# RedBoard_Turbo.net
KiCad netlist of a schematic drawn in EAGLE
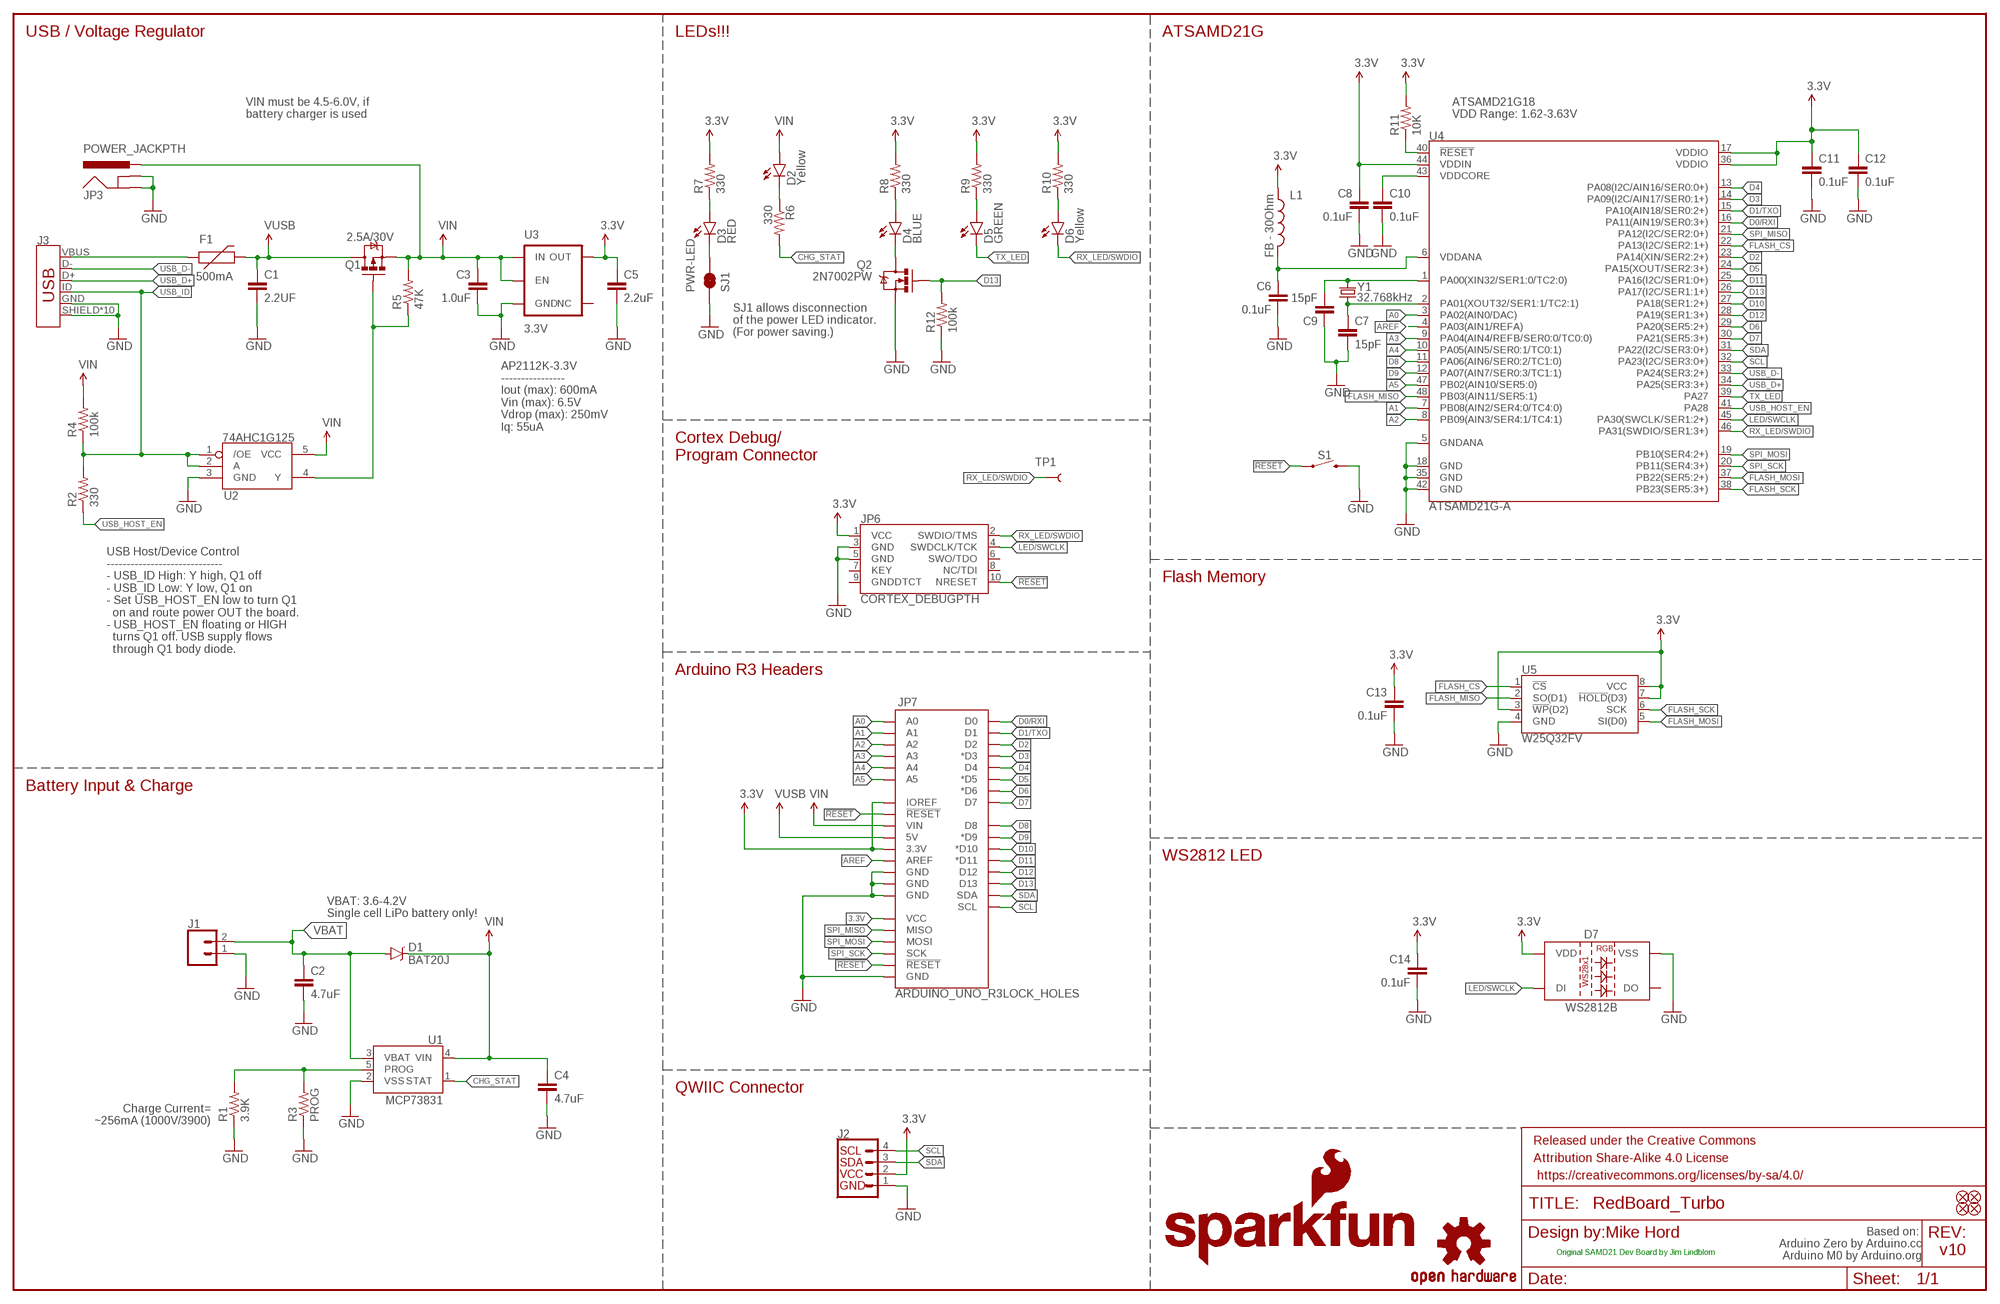
[diagram p0: schematic, sheet 1]

(export (version "E")
  (design (tool "Eeschema 10.0.6"))
  (components
    (comp (ref "C1")
      (value "2.2UF")
      (footprint "eagle-import:1206@1")
      (libsource (lib "eagle-import") (part "2.2UF50V10%(1206)"))
    )
    (comp (ref "C2")
      (value "4.7uF")
      (footprint "eagle-import:0603-CAP")
      (libsource (lib "eagle-import") (part "4.7UF-6.3V-10%(0603)0603"))
    )
    (comp (ref "C3")
      (value "1.0uF")
      (footprint "eagle-import:0805")
      (libsource (lib "eagle-import") (part "1.0UF-0805-25V-10%"))
    )
    (comp (ref "C4")
      (value "4.7uF")
      (footprint "eagle-import:0603-CAP")
      (libsource (lib "eagle-import") (part "4.7UF-6.3V-10%(0603)0603"))
    )
    (comp (ref "C5")
      (value "2.2uF")
      (footprint "eagle-import:0603-CAP")
      (libsource (lib "eagle-import") (part "2.2UF-10V-20%(0603)"))
    )
    (comp (ref "C6")
      (value "0.1uF")
      (footprint "eagle-import:0603-CAP")
      (libsource (lib "eagle-import") (part "0.1UF-25V(+80/-20%)(0603)"))
    )
    (comp (ref "C7")
      (value "15pF")
      (footprint "eagle-import:0603-CAP")
      (libsource (lib "eagle-import") (part "15PF-50V-5%(0603)"))
    )
    (comp (ref "C8")
      (value "0.1uF")
      (footprint "eagle-import:0603-CAP")
      (libsource (lib "eagle-import") (part "0.1UF-25V(+80/-20%)(0603)"))
    )
    (comp (ref "C9")
      (value "15pF")
      (footprint "eagle-import:0603-CAP")
      (libsource (lib "eagle-import") (part "15PF-50V-5%(0603)"))
    )
    (comp (ref "C10")
      (value "0.1uF")
      (footprint "eagle-import:0603-CAP")
      (libsource (lib "eagle-import") (part "0.1UF-25V(+80/-20%)(0603)"))
    )
    (comp (ref "C11")
      (value "0.1uF")
      (footprint "eagle-import:0603-CAP")
      (libsource (lib "eagle-import") (part "0.1UF-25V(+80/-20%)(0603)"))
    )
    (comp (ref "C12")
      (value "0.1uF")
      (footprint "eagle-import:0603-CAP")
      (libsource (lib "eagle-import") (part "0.1UF-25V(+80/-20%)(0603)"))
    )
    (comp (ref "C13")
      (value "0.1uF")
      (footprint "eagle-import:0603-CAP")
      (libsource (lib "eagle-import") (part "0.1UF-25V(+80/-20%)(0603)"))
    )
    (comp (ref "C14")
      (value "0.1uF")
      (footprint "eagle-import:0603-CAP")
      (libsource (lib "eagle-import") (part "0.1UF-25V(+80/-20%)(0603)"))
    )
    (comp (ref "D1")
      (value "BAT20J")
      (footprint "eagle-import:SOD-323")
      (libsource (lib "eagle-import") (part "DIODE-SCHOTTKY-BAT20J"))
    )
    (comp (ref "D2")
      (value "Yellow")
      (footprint "eagle-import:LED-0603")
      (libsource (lib "eagle-import") (part "LED-YELLOW0603"))
    )
    (comp (ref "D3")
      (value "RED")
      (footprint "eagle-import:LED-0603")
      (libsource (lib "eagle-import") (part "LED-RED0603"))
    )
    (comp (ref "D4")
      (value "BLUE")
      (footprint "eagle-import:LED-0603")
      (libsource (lib "eagle-import") (part "LED-BLUE0603"))
    )
    (comp (ref "D5")
      (value "GREEN")
      (footprint "eagle-import:LED-0603")
      (libsource (lib "eagle-import") (part "LED-GREEN0603"))
    )
    (comp (ref "D6")
      (value "Yellow")
      (footprint "eagle-import:LED-0603")
      (libsource (lib "eagle-import") (part "LED-YELLOW0603"))
    )
    (comp (ref "D7")
      (value "WS2812B")
      (footprint "eagle-import:WS2812B")
      (libsource (lib "eagle-import") (part "WS2812B"))
    )
    (comp (ref "F1")
      (value "500mA")
      (footprint "eagle-import:PTC-1206")
      (libsource (lib "eagle-import") (part "PTCSMD"))
    )
    (comp (ref "FID1")
      (value "FIDUCIAL1X2")
      (footprint "eagle-import:FIDUCIAL-1X2")
      (libsource (lib "eagle-import") (part "FIDUCIAL1X2"))
    )
    (comp (ref "FID2")
      (value "FIDUCIAL1X2")
      (footprint "eagle-import:FIDUCIAL-1X2")
      (libsource (lib "eagle-import") (part "FIDUCIAL1X2"))
    )
    (comp (ref "FID3")
      (value "FIDUCIAL1X2")
      (footprint "eagle-import:FIDUCIAL-1X2")
      (libsource (lib "eagle-import") (part "FIDUCIAL1X2"))
    )
    (comp (ref "FID4")
      (value "FIDUCIAL1X2")
      (footprint "eagle-import:FIDUCIAL-1X2")
      (libsource (lib "eagle-import") (part "FIDUCIAL1X2"))
    )
    (comp (ref "FRAME1")
      (value "FRAME-LEDGER")
      (footprint "eagle-import:CREATIVE_COMMONS")
      (libsource (lib "eagle-import") (part "FRAME-LEDGER"))
    )
    (comp (ref "J1")
      (value "CONN_02JST-PTH-2")
      (footprint "eagle-import:JST-2-PTH")
      (libsource (lib "eagle-import") (part "CONN_02JST-PTH-2"))
    )
    (comp (ref "J2")
      (value "QWIIC_CONNECTORJS-1MM")
      (footprint "eagle-import:1X04_1MM_RA")
      (libsource (lib "eagle-import") (part "QWIIC_CONNECTORJS-1MM"))
    )
    (comp (ref "J3")
      (value "USB_MICRO-B_HALF_PTH_MILL")
      (footprint "eagle-import:USB-MICROB-PTH-MILL")
      (libsource (lib "eagle-import") (part "USB_MICRO-B_HALF_PTH_MILL"))
    )
    (comp (ref "JP3")
      (value "POWER_JACKPTH")
      (footprint "eagle-import:POWER_JACK_PTH")
      (libsource (lib "eagle-import") (part "POWER_JACKPTH"))
    )
    (comp (ref "JP6")
      (value "CORTEX_DEBUGPTH")
      (footprint "eagle-import:2X5-PTH-1.27MM")
      (libsource (lib "eagle-import") (part "CORTEX_DEBUGPTH"))
    )
    (comp (ref "JP7")
      (value "ARDUINO_UNO_R3LOCK_HOLES")
      (footprint "eagle-import:ARDUINO_R3_LOCK_HOLES")
      (libsource (lib "eagle-import") (part "ARDUINO_UNO_R3LOCK_HOLES"))
    )
    (comp (ref "L1")
      (value "FB - 30Ohm")
      (footprint "eagle-import:0603")
      (libsource (lib "eagle-import") (part "INDUCTOR0603"))
    )
    (comp (ref "LOGO1")
      (value "SFE_LOGO_NAME_FLAME.2_INCH")
      (footprint "eagle-import:SFE_LOGO_NAME_FLAME_.2")
      (libsource (lib "eagle-import") (part "SFE_LOGO_NAME_FLAME.2_INCH"))
    )
    (comp (ref "LOGO2")
      (value "SFE_LOGO_NAME_FLAME.3_INCH")
      (footprint "eagle-import:SFE_LOGO_NAME_FLAME_.3")
      (libsource (lib "eagle-import") (part "SFE_LOGO_NAME_FLAME.3_INCH"))
    )
    (comp (ref "LOGO3")
      (value "OSHW-LOGOS")
      (footprint "eagle-import:OSHW-LOGO-S")
      (libsource (lib "eagle-import") (part "OSHW-LOGOS"))
    )
    (comp (ref "LOGO4")
      (value "OSHW-LOGOL")
      (footprint "eagle-import:OSHW-LOGO-L")
      (libsource (lib "eagle-import") (part "OSHW-LOGOL"))
    )
    (comp (ref "Q1")
      (value "2.5A/30V")
      (footprint "eagle-import:SOT23-3")
      (libsource (lib "eagle-import") (part "MOSFET-PCHANNELDMG2307L"))
    )
    (comp (ref "Q2")
      (value "2N7002PW")
      (footprint "eagle-import:SOT323")
      (libsource (lib "eagle-import") (part "MOSFET-NCHANNEL2N7002PW"))
    )
    (comp (ref "R1")
      (value "3.9K")
      (footprint "eagle-import:0603")
      (libsource (lib "eagle-import") (part "3.9KOHM1/10W1%(0603)"))
    )
    (comp (ref "R2")
      (value "330")
      (footprint "eagle-import:0603-RES")
      (libsource (lib "eagle-import") (part "330OHM1/10W1%(0603)"))
    )
    (comp (ref "R3")
      (value "PROG")
      (footprint "eagle-import:1_6W-RES")
      (libsource (lib "eagle-import") (part "RESISTORPTH-1/6W"))
    )
    (comp (ref "R4")
      (value "100k")
      (footprint "eagle-import:0603-RES")
      (libsource (lib "eagle-import") (part "100KOHM-1/10W-1%(0603)"))
    )
    (comp (ref "R5")
      (value "47K")
      (footprint "eagle-import:0603-RES")
      (libsource (lib "eagle-import") (part "47KOHM1/10W1%(0603)"))
    )
    (comp (ref "R6")
      (value "330")
      (footprint "eagle-import:0603-RES")
      (libsource (lib "eagle-import") (part "330OHM1/10W1%(0603)"))
    )
    (comp (ref "R7")
      (value "330")
      (footprint "eagle-import:0603-RES")
      (libsource (lib "eagle-import") (part "330OHM1/10W1%(0603)"))
    )
    (comp (ref "R8")
      (value "330")
      (footprint "eagle-import:0603-RES")
      (libsource (lib "eagle-import") (part "330OHM1/10W1%(0603)"))
    )
    (comp (ref "R9")
      (value "330")
      (footprint "eagle-import:0603-RES")
      (libsource (lib "eagle-import") (part "330OHM1/10W1%(0603)"))
    )
    (comp (ref "R10")
      (value "330")
      (footprint "eagle-import:0603-RES")
      (libsource (lib "eagle-import") (part "330OHM1/10W1%(0603)"))
    )
    (comp (ref "R11")
      (value "10K")
      (footprint "eagle-import:0603-RES")
      (libsource (lib "eagle-import") (part "10KOHM-1/10W-1%(0603)0603"))
    )
    (comp (ref "R12")
      (value "100k")
      (footprint "eagle-import:0603-RES")
      (libsource (lib "eagle-import") (part "100KOHM-1/10W-1%(0603)"))
    )
    (comp (ref "S1")
      (value "MOMENTARY-SWITCH-SPST-SMD-5.2-TALL-REDUNDANT")
      (footprint "eagle-import:TACTILE_SWITCH_SMD_5.2MM")
      (libsource (lib "eagle-import") (part "MOMENTARY-SWITCH-SPST-SMD-5.2-TALL-REDUNDANT"))
    )
    (comp (ref "SJ1")
      (value "PWR-LED")
      (footprint "eagle-import:PAD-JUMPER-2-NC_BY_TRACE_NO_SILK")
      (libsource (lib "eagle-import") (part "JUMPER-PAD-2-NC_BY_TRACENO_SILK"))
    )
    (comp (ref "TP1")
      (value "TEST-POINTTP_15TH_THRU")
      (footprint "eagle-import:TP_15TH")
      (libsource (lib "eagle-import") (part "TEST-POINTTP_15TH_THRU"))
    )
    (comp (ref "U1")
      (value "MCP73831")
      (footprint "eagle-import:SOT23-5")
      (libsource (lib "eagle-import") (part "MCP73831"))
    )
    (comp (ref "U2")
      (value "74AHC1G125")
      (footprint "eagle-import:SOT23-5")
      (libsource (lib "eagle-import") (part "74AHC1G125"))
    )
    (comp (ref "U3")
      (value "3.3V")
      (footprint "eagle-import:SOT23-5")
      (libsource (lib "eagle-import") (part "V_REG_AP2112K-3.3V"))
    )
    (comp (ref "U4")
      (value "ATSAMD21G-A")
      (footprint "eagle-import:TQFP-48")
      (libsource (lib "eagle-import") (part "ATSAMD21G-A"))
    )
    (comp (ref "U5")
      (value "W25Q32FV")
      (footprint "eagle-import:SOIC-8")
      (libsource (lib "eagle-import") (part "W25Q32FVSS"))
    )
    (comp (ref "Y1")
      (value "32.768kHz")
      (footprint "eagle-import:CRYSTAL-SMD-3.2X1.5MM")
      (libsource (lib "eagle-import") (part "CRYSTAL3.2X1.5MM"))
    )
  )
  (nets
    (net (code "1") (name "/~{RESET}") (class "Default")
      (node (ref "JP6") (pin "10") (pinfunction "NRESET_10") (pintype "bidirectional"))
      (node (ref "JP7") (pin "RESET@1") (pinfunction "~{RESET}_RESET@1") (pintype "bidirectional"))
      (node (ref "JP7") (pin "RESET@2") (pinfunction "~{RESET}_RESET@2") (pintype "bidirectional"))
      (node (ref "R11") (pin "1") (pinfunction "1_1") (pintype "passive"))
      (node (ref "S1") (pin "1") (pinfunction "1_1") (pintype "passive"))
      (node (ref "S1") (pin "2") (pinfunction "1_2") (pintype "passive"))
      (node (ref "U4") (pin "40") (pinfunction "~{RESET}_40") (pintype "bidirectional"))
    )
    (net (code "2") (name "3.3V") (class "Default")
      (node (ref "C11") (pin "1") (pinfunction "1_1") (pintype "passive"))
      (node (ref "C12") (pin "1") (pinfunction "1_1") (pintype "passive"))
      (node (ref "C13") (pin "1") (pinfunction "1_1") (pintype "passive"))
      (node (ref "C14") (pin "1") (pinfunction "1_1") (pintype "passive"))
      (node (ref "C5") (pin "1") (pinfunction "1_1") (pintype "passive"))
      (node (ref "C8") (pin "1") (pinfunction "1_1") (pintype "passive"))
      (node (ref "D7") (pin "1") (pinfunction "VDD_1") (pintype "bidirectional"))
      (node (ref "J2") (pin "2") (pinfunction "2_2") (pintype "power_in"))
      (node (ref "JP6") (pin "1") (pinfunction "VCC_1") (pintype "bidirectional"))
      (node (ref "JP7") (pin "3.3V") (pinfunction "3.3V_3.3V") (pintype "bidirectional"))
      (node (ref "JP7") (pin "IOREF") (pinfunction "IOREF_IOREF") (pintype "bidirectional"))
      (node (ref "JP7") (pin "VCC") (pinfunction "VCC_VCC") (pintype "bidirectional"))
      (node (ref "L1") (pin "1") (pinfunction "1_1") (pintype "passive"))
      (node (ref "R10") (pin "2") (pinfunction "2_2") (pintype "passive"))
      (node (ref "R11") (pin "2") (pinfunction "2_2") (pintype "passive"))
      (node (ref "R7") (pin "2") (pinfunction "2_2") (pintype "passive"))
      (node (ref "R8") (pin "2") (pinfunction "2_2") (pintype "passive"))
      (node (ref "R9") (pin "2") (pinfunction "2_2") (pintype "passive"))
      (node (ref "U3") (pin "5") (pinfunction "OUT_5") (pintype "passive"))
      (node (ref "U4") (pin "17") (pinfunction "VDDIO_17") (pintype "bidirectional"))
      (node (ref "U4") (pin "36") (pinfunction "VDDIO_36") (pintype "bidirectional"))
      (node (ref "U4") (pin "44") (pinfunction "VDDIN_44") (pintype "bidirectional"))
      (node (ref "U5") (pin "3") (pinfunction "~{WP}(D2)_3") (pintype "bidirectional"))
      (node (ref "U5") (pin "7") (pinfunction "~{HOLD}(D3)_7") (pintype "bidirectional"))
      (node (ref "U5") (pin "8") (pinfunction "VCC_8") (pintype "bidirectional"))
    )
    (net (code "3") (name "A0") (class "Default")
      (node (ref "JP7") (pin "A0") (pinfunction "A0_A0") (pintype "bidirectional"))
      (node (ref "U4") (pin "3") (pinfunction "PA02(AIN0/DAC)_3") (pintype "bidirectional"))
    )
    (net (code "4") (name "A1") (class "Default")
      (node (ref "JP7") (pin "A1") (pinfunction "A1_A1") (pintype "bidirectional"))
      (node (ref "U4") (pin "7") (pinfunction "PB08(AIN2/SER4:0/TC4:0)_7") (pintype "bidirectional"))
    )
    (net (code "5") (name "A2") (class "Default")
      (node (ref "JP7") (pin "A2") (pinfunction "A2_A2") (pintype "bidirectional"))
      (node (ref "U4") (pin "8") (pinfunction "PB09(AIN3/SER4:1/TC4:1)_8") (pintype "bidirectional"))
    )
    (net (code "6") (name "A3") (class "Default")
      (node (ref "JP7") (pin "A3") (pinfunction "A3_A3") (pintype "bidirectional"))
      (node (ref "U4") (pin "9") (pinfunction "PA04(AIN4/REFB/SER0:0/TC0:0)_9") (pintype "bidirectional"))
    )
    (net (code "7") (name "A4") (class "Default")
      (node (ref "JP7") (pin "A4") (pinfunction "A4_A4") (pintype "bidirectional"))
      (node (ref "U4") (pin "10") (pinfunction "PA05(AIN5/SER0:1/TC0:1)_10") (pintype "bidirectional"))
    )
    (net (code "8") (name "A5") (class "Default")
      (node (ref "JP7") (pin "A5") (pinfunction "A5_A5") (pintype "bidirectional"))
      (node (ref "U4") (pin "47") (pinfunction "PB02(AIN10/SER5:0)_47") (pintype "bidirectional"))
    )
    (net (code "9") (name "AREF") (class "Default")
      (node (ref "JP7") (pin "AREF") (pinfunction "AREF_AREF") (pintype "bidirectional"))
      (node (ref "U4") (pin "4") (pinfunction "PA03(AIN1/REFA)_4") (pintype "bidirectional"))
    )
    (net (code "10") (name "CHG_STAT") (class "Default")
      (node (ref "R6") (pin "2") (pinfunction "2_2") (pintype "passive"))
      (node (ref "U1") (pin "1") (pinfunction "STAT_1") (pintype "output"))
    )
    (net (code "11") (name "D0{slash}RXI") (class "Default")
      (node (ref "JP7") (pin "D0") (pinfunction "D0_D0") (pintype "bidirectional"))
      (node (ref "U4") (pin "16") (pinfunction "PA11(AIN19/SER0:3+)_16") (pintype "bidirectional"))
    )
    (net (code "12") (name "D1{slash}TXO") (class "Default")
      (node (ref "JP7") (pin "D1") (pinfunction "D1_D1") (pintype "bidirectional"))
      (node (ref "U4") (pin "15") (pinfunction "PA10(AIN18/SER0:2+)_15") (pintype "bidirectional"))
    )
    (net (code "13") (name "D2") (class "Default")
      (node (ref "JP7") (pin "D2") (pinfunction "D2_D2") (pintype "bidirectional"))
      (node (ref "U4") (pin "23") (pinfunction "PA14(XIN/SER2:2+)_23") (pintype "bidirectional"))
    )
    (net (code "14") (name "D3") (class "Default")
      (node (ref "JP7") (pin "D3") (pinfunction "*D3_D3") (pintype "bidirectional"))
      (node (ref "U4") (pin "14") (pinfunction "PA09(I2C/AIN17/SER0:1+)_14") (pintype "bidirectional"))
    )
    (net (code "15") (name "D4") (class "Default")
      (node (ref "JP7") (pin "D4") (pinfunction "D4_D4") (pintype "bidirectional"))
      (node (ref "U4") (pin "13") (pinfunction "PA08(I2C/AIN16/SER0:0+)_13") (pintype "bidirectional"))
    )
    (net (code "16") (name "D5") (class "Default")
      (node (ref "JP7") (pin "D5") (pinfunction "*D5_D5") (pintype "bidirectional"))
      (node (ref "U4") (pin "24") (pinfunction "PA15(XOUT/SER2:3+)_24") (pintype "bidirectional"))
    )
    (net (code "17") (name "D6") (class "Default")
      (node (ref "JP7") (pin "D6") (pinfunction "*D6_D6") (pintype "bidirectional"))
      (node (ref "U4") (pin "29") (pinfunction "PA20(SER5:2+)_29") (pintype "bidirectional"))
    )
    (net (code "18") (name "D7") (class "Default")
      (node (ref "JP7") (pin "D7") (pinfunction "D7_D7") (pintype "bidirectional"))
      (node (ref "U4") (pin "30") (pinfunction "PA21(SER5:3+)_30") (pintype "bidirectional"))
    )
    (net (code "19") (name "D8") (class "Default")
      (node (ref "JP7") (pin "D8") (pinfunction "D8_D8") (pintype "bidirectional"))
      (node (ref "U4") (pin "11") (pinfunction "PA06(AIN6/SER0:2/TC1:0)_11") (pintype "bidirectional"))
    )
    (net (code "20") (name "D9") (class "Default")
      (node (ref "JP7") (pin "D9") (pinfunction "*D9_D9") (pintype "bidirectional"))
      (node (ref "U4") (pin "12") (pinfunction "PA07(AIN7/SER0:3/TC1:1)_12") (pintype "bidirectional"))
    )
    (net (code "21") (name "D10") (class "Default")
      (node (ref "JP7") (pin "D10") (pinfunction "*D10_D10") (pintype "bidirectional"))
      (node (ref "U4") (pin "27") (pinfunction "PA18(SER1:2+)_27") (pintype "bidirectional"))
    )
    (net (code "22") (name "D11") (class "Default")
      (node (ref "JP7") (pin "D11") (pinfunction "*D11_D11") (pintype "bidirectional"))
      (node (ref "U4") (pin "25") (pinfunction "PA16(I2C/SER1:0+)_25") (pintype "bidirectional"))
    )
    (net (code "23") (name "D12") (class "Default")
      (node (ref "JP7") (pin "D12") (pinfunction "D12_D12") (pintype "bidirectional"))
      (node (ref "U4") (pin "28") (pinfunction "PA19(SER1:3+)_28") (pintype "bidirectional"))
    )
    (net (code "24") (name "D13") (class "Default")
      (node (ref "JP7") (pin "D13") (pinfunction "D13_D13") (pintype "bidirectional"))
      (node (ref "Q2") (pin "1") (pinfunction "G_1") (pintype "passive"))
      (node (ref "R12") (pin "2") (pinfunction "2_2") (pintype "passive"))
      (node (ref "U4") (pin "26") (pinfunction "PA17(I2C/SER1:1+)_26") (pintype "bidirectional"))
    )
    (net (code "25") (name "FLASH_CS") (class "Default")
      (node (ref "U4") (pin "22") (pinfunction "PA13(I2C/SER2:1+)_22") (pintype "bidirectional"))
      (node (ref "U5") (pin "1") (pinfunction "~{CS}_1") (pintype "bidirectional"))
    )
    (net (code "26") (name "FLASH_MISO") (class "Default")
      (node (ref "U4") (pin "48") (pinfunction "PB03(AIN11/SER5:1)_48") (pintype "bidirectional"))
      (node (ref "U5") (pin "2") (pinfunction "SO(D1)_2") (pintype "bidirectional"))
    )
    (net (code "27") (name "FLASH_MOSI") (class "Default")
      (node (ref "U4") (pin "37") (pinfunction "PB22(SER5:2+)_37") (pintype "bidirectional"))
      (node (ref "U5") (pin "5") (pinfunction "SI(D0)_5") (pintype "bidirectional"))
    )
    (net (code "28") (name "FLASH_SCK") (class "Default")
      (node (ref "U4") (pin "38") (pinfunction "PB23(SER5:3+)_38") (pintype "bidirectional"))
      (node (ref "U5") (pin "6") (pinfunction "SCK_6") (pintype "bidirectional"))
    )
    (net (code "29") (name "GND") (class "Default")
      (node (ref "C1") (pin "2") (pinfunction "2_2") (pintype "passive"))
      (node (ref "C10") (pin "2") (pinfunction "2_2") (pintype "passive"))
      (node (ref "C11") (pin "2") (pinfunction "2_2") (pintype "passive"))
      (node (ref "C12") (pin "2") (pinfunction "2_2") (pintype "passive"))
      (node (ref "C13") (pin "2") (pinfunction "2_2") (pintype "passive"))
      (node (ref "C14") (pin "2") (pinfunction "2_2") (pintype "passive"))
      (node (ref "C2") (pin "2") (pinfunction "2_2") (pintype "passive"))
      (node (ref "C3") (pin "2") (pinfunction "2_2") (pintype "passive"))
      (node (ref "C4") (pin "2") (pinfunction "2_2") (pintype "passive"))
      (node (ref "C5") (pin "2") (pinfunction "2_2") (pintype "passive"))
      (node (ref "C6") (pin "2") (pinfunction "2_2") (pintype "passive"))
      (node (ref "C7") (pin "2") (pinfunction "2_2") (pintype "passive"))
      (node (ref "C8") (pin "2") (pinfunction "2_2") (pintype "passive"))
      (node (ref "C9") (pin "1") (pinfunction "1_1") (pintype "passive"))
      (node (ref "D7") (pin "3") (pinfunction "VSS_3") (pintype "bidirectional"))
      (node (ref "J1") (pin "1") (pinfunction "1_1") (pintype "passive"))
      (node (ref "J2") (pin "1") (pinfunction "1_1") (pintype "power_in"))
      (node (ref "J3") (pin "GND") (pinfunction "GND_GND") (pintype "power_in"))
      (node (ref "J3") (pin "SHIELD") (pinfunction "SHIELD_SHIELD") (pintype "bidirectional"))
      (node (ref "J3") (pin "SHIELD10") (pinfunction "SHIELD_SHIELD10") (pintype "bidirectional"))
      (node (ref "J3") (pin "SHIELD2") (pinfunction "SHIELD_SHIELD2") (pintype "bidirectional"))
      (node (ref "J3") (pin "SHIELD3") (pinfunction "SHIELD_SHIELD3") (pintype "bidirectional"))
      (node (ref "J3") (pin "SHIELD4") (pinfunction "SHIELD_SHIELD4") (pintype "bidirectional"))
      (node (ref "J3") (pin "SHIELD5") (pinfunction "SHIELD_SHIELD5") (pintype "bidirectional"))
      (node (ref "J3") (pin "SHIELD6") (pinfunction "SHIELD_SHIELD6") (pintype "bidirectional"))
      (node (ref "J3") (pin "SHIELD7") (pinfunction "SHIELD_SHIELD7") (pintype "bidirectional"))
      (node (ref "J3") (pin "SHIELD8") (pinfunction "SHIELD_SHIELD8") (pintype "bidirectional"))
      (node (ref "J3") (pin "SHIELD9") (pinfunction "SHIELD_SHIELD9") (pintype "bidirectional"))
      (node (ref "JP3") (pin "GND") (pinfunction "GND_GND") (pintype "bidirectional"))
      (node (ref "JP3") (pin "GNDBREAK") (pinfunction "GNDBREAK_GNDBREAK") (pintype "bidirectional"))
      (node (ref "JP6") (pin "3") (pinfunction "GND_3") (pintype "bidirectional"))
      (node (ref "JP6") (pin "5") (pinfunction "GND_5") (pintype "bidirectional"))
      (node (ref "JP7") (pin "GND@1") (pinfunction "GND_GND@1") (pintype "bidirectional"))
      (node (ref "JP7") (pin "GND@2") (pinfunction "GND_GND@2") (pintype "bidirectional"))
      (node (ref "JP7") (pin "GND@3") (pinfunction "GND_GND@3") (pintype "bidirectional"))
      (node (ref "JP7") (pin "GND@4") (pinfunction "GND_GND@4") (pintype "bidirectional"))
      (node (ref "Q2") (pin "2") (pinfunction "S_2") (pintype "passive"))
      (node (ref "R1") (pin "1") (pinfunction "1_1") (pintype "passive"))
      (node (ref "R12") (pin "1") (pinfunction "1_1") (pintype "passive"))
      (node (ref "R3") (pin "1") (pinfunction "1_1") (pintype "passive"))
      (node (ref "S1") (pin "3") (pinfunction "2_3") (pintype "passive"))
      (node (ref "S1") (pin "4") (pinfunction "2_4") (pintype "passive"))
      (node (ref "SJ1") (pin "1") (pinfunction "1_1") (pintype "passive"))
      (node (ref "U1") (pin "2") (pinfunction "VSS_2") (pintype "power_in"))
      (node (ref "U2") (pin "3") (pinfunction "GND_3") (pintype "bidirectional"))
      (node (ref "U3") (pin "2") (pinfunction "GND_2") (pintype "input"))
      (node (ref "U4") (pin "18") (pinfunction "GND_18") (pintype "bidirectional"))
      (node (ref "U4") (pin "35") (pinfunction "GND_35") (pintype "bidirectional"))
      (node (ref "U4") (pin "42") (pinfunction "GND_42") (pintype "bidirectional"))
      (node (ref "U4") (pin "5") (pinfunction "GNDANA_5") (pintype "bidirectional"))
      (node (ref "U5") (pin "4") (pinfunction "GND_4") (pintype "bidirectional"))
    )
    (net (code "30") (name "LED{slash}SWCLK") (class "Default")
      (node (ref "D7") (pin "4") (pinfunction "DI_4") (pintype "bidirectional"))
      (node (ref "JP6") (pin "4") (pinfunction "SWDCLK/TCK_4") (pintype "bidirectional"))
      (node (ref "U4") (pin "45") (pinfunction "PA30(SWCLK/SER1:2+)_45") (pintype "bidirectional"))
    )
    (net (code "31") (name "Net-(D2-PadC)") (class "Default")
      (node (ref "D2") (pin "C") (pinfunction "C_C") (pintype "passive"))
      (node (ref "R6") (pin "1") (pinfunction "1_1") (pintype "passive"))
    )
    (net (code "32") (name "Net-(D3-PadA)") (class "Default")
      (node (ref "D3") (pin "A") (pinfunction "A_A") (pintype "passive"))
      (node (ref "R7") (pin "1") (pinfunction "1_1") (pintype "passive"))
    )
    (net (code "33") (name "Net-(D3-PadC)") (class "Default")
      (node (ref "D3") (pin "C") (pinfunction "C_C") (pintype "passive"))
      (node (ref "SJ1") (pin "2") (pinfunction "2_2") (pintype "passive"))
    )
    (net (code "34") (name "Net-(D4-PadA)") (class "Default")
      (node (ref "D4") (pin "A") (pinfunction "A_A") (pintype "passive"))
      (node (ref "R8") (pin "1") (pinfunction "1_1") (pintype "passive"))
    )
    (net (code "35") (name "Net-(D5-PadA)") (class "Default")
      (node (ref "D5") (pin "A") (pinfunction "A_A") (pintype "passive"))
      (node (ref "R9") (pin "1") (pinfunction "1_1") (pintype "passive"))
    )
    (net (code "36") (name "Net-(D6-PadA)") (class "Default")
      (node (ref "D6") (pin "A") (pinfunction "A_A") (pintype "passive"))
      (node (ref "R10") (pin "1") (pinfunction "1_1") (pintype "passive"))
    )
    (net (code "37") (name "Net-(F1-Pad1)") (class "Default")
      (node (ref "F1") (pin "1") (pinfunction "1_1") (pintype "bidirectional"))
      (node (ref "J3") (pin "VBUS") (pinfunction "VBUS_VBUS") (pintype "power_in"))
    )
    (net (code "38") (name "Net-(Q1-G)") (class "Default")
      (node (ref "Q1") (pin "1") (pinfunction "G_1") (pintype "passive"))
      (node (ref "R5") (pin "1") (pinfunction "1_1") (pintype "passive"))
      (node (ref "U2") (pin "4") (pinfunction "Y_4") (pintype "bidirectional"))
    )
    (net (code "39") (name "Net-(Q2-D)") (class "Default")
      (node (ref "D4") (pin "C") (pinfunction "C_C") (pintype "passive"))
      (node (ref "Q2") (pin "3") (pinfunction "D_3") (pintype "passive"))
    )
    (net (code "40") (name "Net-(U1-PROG)") (class "Default")
      (node (ref "R1") (pin "2") (pinfunction "2_2") (pintype "passive"))
      (node (ref "R3") (pin "2") (pinfunction "2_2") (pintype "passive"))
      (node (ref "U1") (pin "5") (pinfunction "PROG_5") (pintype "input"))
    )
    (net (code "41") (name "Net-(U4-PA00(XIN32{slash}SER1:0{slash}TC2:0))") (class "Default")
      (node (ref "C9") (pin "2") (pinfunction "2_2") (pintype "passive"))
      (node (ref "U4") (pin "1") (pinfunction "PA00(XIN32/SER1:0/TC2:0)_1") (pintype "bidirectional"))
      (node (ref "Y1") (pin "P$2") (pinfunction "2_P$2") (pintype "passive"))
    )
    (net (code "42") (name "Net-(U4-PA01(XOUT32{slash}SER1:1{slash}TC2:1))") (class "Default")
      (node (ref "C7") (pin "1") (pinfunction "1_1") (pintype "passive"))
      (node (ref "U4") (pin "2") (pinfunction "PA01(XOUT32/SER1:1/TC2:1)_2") (pintype "bidirectional"))
      (node (ref "Y1") (pin "P$1") (pinfunction "1_P$1") (pintype "passive"))
    )
    (net (code "43") (name "Net-(U4-VDDANA)") (class "Default")
      (node (ref "C6") (pin "1") (pinfunction "1_1") (pintype "passive"))
      (node (ref "L1") (pin "2") (pinfunction "2_2") (pintype "passive"))
      (node (ref "U4") (pin "6") (pinfunction "VDDANA_6") (pintype "bidirectional"))
    )
    (net (code "44") (name "Net-(U4-VDDCORE)") (class "Default")
      (node (ref "C10") (pin "1") (pinfunction "1_1") (pintype "passive"))
      (node (ref "U4") (pin "43") (pinfunction "VDDCORE_43") (pintype "bidirectional"))
    )
    (net (code "45") (name "RX_LED{slash}SWDIO") (class "Default")
      (node (ref "D6") (pin "C") (pinfunction "C_C") (pintype "passive"))
      (node (ref "JP6") (pin "2") (pinfunction "SWDIO/TMS_2") (pintype "bidirectional"))
      (node (ref "TP1") (pin "P$1") (pinfunction "1_P$1") (pintype "bidirectional"))
      (node (ref "U4") (pin "46") (pinfunction "PA31(SWDIO/SER1:3+)_46") (pintype "bidirectional"))
    )
    (net (code "46") (name "SCL") (class "Default")
      (node (ref "J2") (pin "4") (pinfunction "4_4") (pintype "passive"))
      (node (ref "JP7") (pin "SCL") (pinfunction "SCL_SCL") (pintype "bidirectional"))
      (node (ref "U4") (pin "32") (pinfunction "PA23(I2C/SER3:0+)_32") (pintype "bidirectional"))
    )
    (net (code "47") (name "SDA") (class "Default")
      (node (ref "J2") (pin "3") (pinfunction "3_3") (pintype "passive"))
      (node (ref "JP7") (pin "SDA") (pinfunction "SDA_SDA") (pintype "bidirectional"))
      (node (ref "U4") (pin "31") (pinfunction "PA22(I2C/SER3:0+)_31") (pintype "bidirectional"))
    )
    (net (code "48") (name "SPI_MISO") (class "Default")
      (node (ref "JP7") (pin "MISO") (pinfunction "MISO_MISO") (pintype "bidirectional"))
      (node (ref "U4") (pin "21") (pinfunction "PA12(I2C/SER2:0+)_21") (pintype "bidirectional"))
    )
    (net (code "49") (name "SPI_MOSI") (class "Default")
      (node (ref "JP7") (pin "MOSI") (pinfunction "MOSI_MOSI") (pintype "bidirectional"))
      (node (ref "U4") (pin "19") (pinfunction "PB10(SER4:2+)_19") (pintype "bidirectional"))
    )
    (net (code "50") (name "SPI_SCK") (class "Default")
      (node (ref "JP7") (pin "SCK") (pinfunction "SCK_SCK") (pintype "bidirectional"))
      (node (ref "U4") (pin "20") (pinfunction "PB11(SER4:3+)_20") (pintype "bidirectional"))
    )
    (net (code "51") (name "TX_LED") (class "Default")
      (node (ref "D5") (pin "C") (pinfunction "C_C") (pintype "passive"))
      (node (ref "U4") (pin "39") (pinfunction "PA27_39") (pintype "bidirectional"))
    )
    (net (code "52") (name "USB_D+") (class "Default")
      (node (ref "J3") (pin "D+") (pinfunction "D+_D+") (pintype "bidirectional"))
      (node (ref "U4") (pin "34") (pinfunction "PA25(SER3:3+)_34") (pintype "bidirectional"))
    )
    (net (code "53") (name "USB_D-") (class "Default")
      (node (ref "J3") (pin "D-") (pinfunction "D-_D-") (pintype "bidirectional"))
      (node (ref "U4") (pin "33") (pinfunction "PA24(SER3:2+)_33") (pintype "bidirectional"))
    )
    (net (code "54") (name "USB_HOST_EN") (class "Default")
      (node (ref "R2") (pin "1") (pinfunction "1_1") (pintype "passive"))
      (node (ref "U4") (pin "41") (pinfunction "PA28_41") (pintype "bidirectional"))
    )
    (net (code "55") (name "USB_ID") (class "Default")
      (node (ref "J3") (pin "ID") (pinfunction "ID_ID") (pintype "bidirectional"))
      (node (ref "R2") (pin "2") (pinfunction "2_2") (pintype "passive"))
      (node (ref "R4") (pin "1") (pinfunction "1_1") (pintype "passive"))
      (node (ref "U2") (pin "1") (pinfunction "/OE_1") (pintype "bidirectional"))
      (node (ref "U2") (pin "2") (pinfunction "A_2") (pintype "bidirectional"))
    )
    (net (code "56") (name "VBAT") (class "Default")
      (node (ref "C2") (pin "1") (pinfunction "1_1") (pintype "passive"))
      (node (ref "D1") (pin "A") (pinfunction "A_A") (pintype "passive"))
      (node (ref "J1") (pin "2") (pinfunction "2_2") (pintype "passive"))
      (node (ref "U1") (pin "3") (pinfunction "VBAT_3") (pintype "power_in"))
    )
    (net (code "57") (name "VIN") (class "Default")
      (node (ref "C3") (pin "1") (pinfunction "1_1") (pintype "passive"))
      (node (ref "C4") (pin "1") (pinfunction "1_1") (pintype "passive"))
      (node (ref "D1") (pin "C") (pinfunction "C_C") (pintype "passive"))
      (node (ref "D2") (pin "A") (pinfunction "A_A") (pintype "passive"))
      (node (ref "JP3") (pin "PWR") (pinfunction "PWR_PWR") (pintype "bidirectional"))
      (node (ref "JP7") (pin "VIN") (pinfunction "VIN_VIN") (pintype "bidirectional"))
      (node (ref "Q1") (pin "2") (pinfunction "S_2") (pintype "passive"))
      (node (ref "R4") (pin "2") (pinfunction "2_2") (pintype "passive"))
      (node (ref "R5") (pin "2") (pinfunction "2_2") (pintype "passive"))
      (node (ref "U1") (pin "4") (pinfunction "VIN_4") (pintype "power_in"))
      (node (ref "U2") (pin "5") (pinfunction "VCC_5") (pintype "bidirectional"))
      (node (ref "U3") (pin "1") (pinfunction "IN_1") (pintype "input"))
      (node (ref "U3") (pin "3") (pinfunction "EN_3") (pintype "input"))
    )
    (net (code "58") (name "VUSB") (class "Default")
      (node (ref "C1") (pin "1") (pinfunction "1_1") (pintype "passive"))
      (node (ref "F1") (pin "2") (pinfunction "2_2") (pintype "bidirectional"))
      (node (ref "JP7") (pin "5V") (pinfunction "5V_5V") (pintype "bidirectional"))
      (node (ref "Q1") (pin "3") (pinfunction "D_3") (pintype "passive"))
    )
    (net (code "59") (name "unconnected-(D7-DO-Pad2)") (class "Default")
      (node (ref "D7") (pin "2") (pinfunction "DO_2") (pintype "bidirectional"))
    )
    (net (code "60") (name "unconnected-(JP6-GNDDTCT-Pad9)") (class "Default")
      (node (ref "JP6") (pin "9") (pinfunction "GNDDTCT_9") (pintype "bidirectional"))
    )
    (net (code "61") (name "unconnected-(JP6-KEY-Pad7)") (class "Default")
      (node (ref "JP6") (pin "7") (pinfunction "KEY_7") (pintype "bidirectional"))
    )
    (net (code "62") (name "unconnected-(JP6-NC{slash}TDI-Pad8)") (class "Default")
      (node (ref "JP6") (pin "8") (pinfunction "NC/TDI_8") (pintype "bidirectional"))
    )
    (net (code "63") (name "unconnected-(JP6-SWO{slash}TDO-Pad6)") (class "Default")
      (node (ref "JP6") (pin "6") (pinfunction "SWO/TDO_6") (pintype "bidirectional"))
    )
    (net (code "64") (name "unconnected-(U3-NC-Pad4)") (class "Default")
      (node (ref "U3") (pin "4") (pinfunction "NC_4") (pintype "input"))
    )
  )
)
